# slotESCsmall_S02.net
KiCad netlist of a schematic drawn in Altium Designer
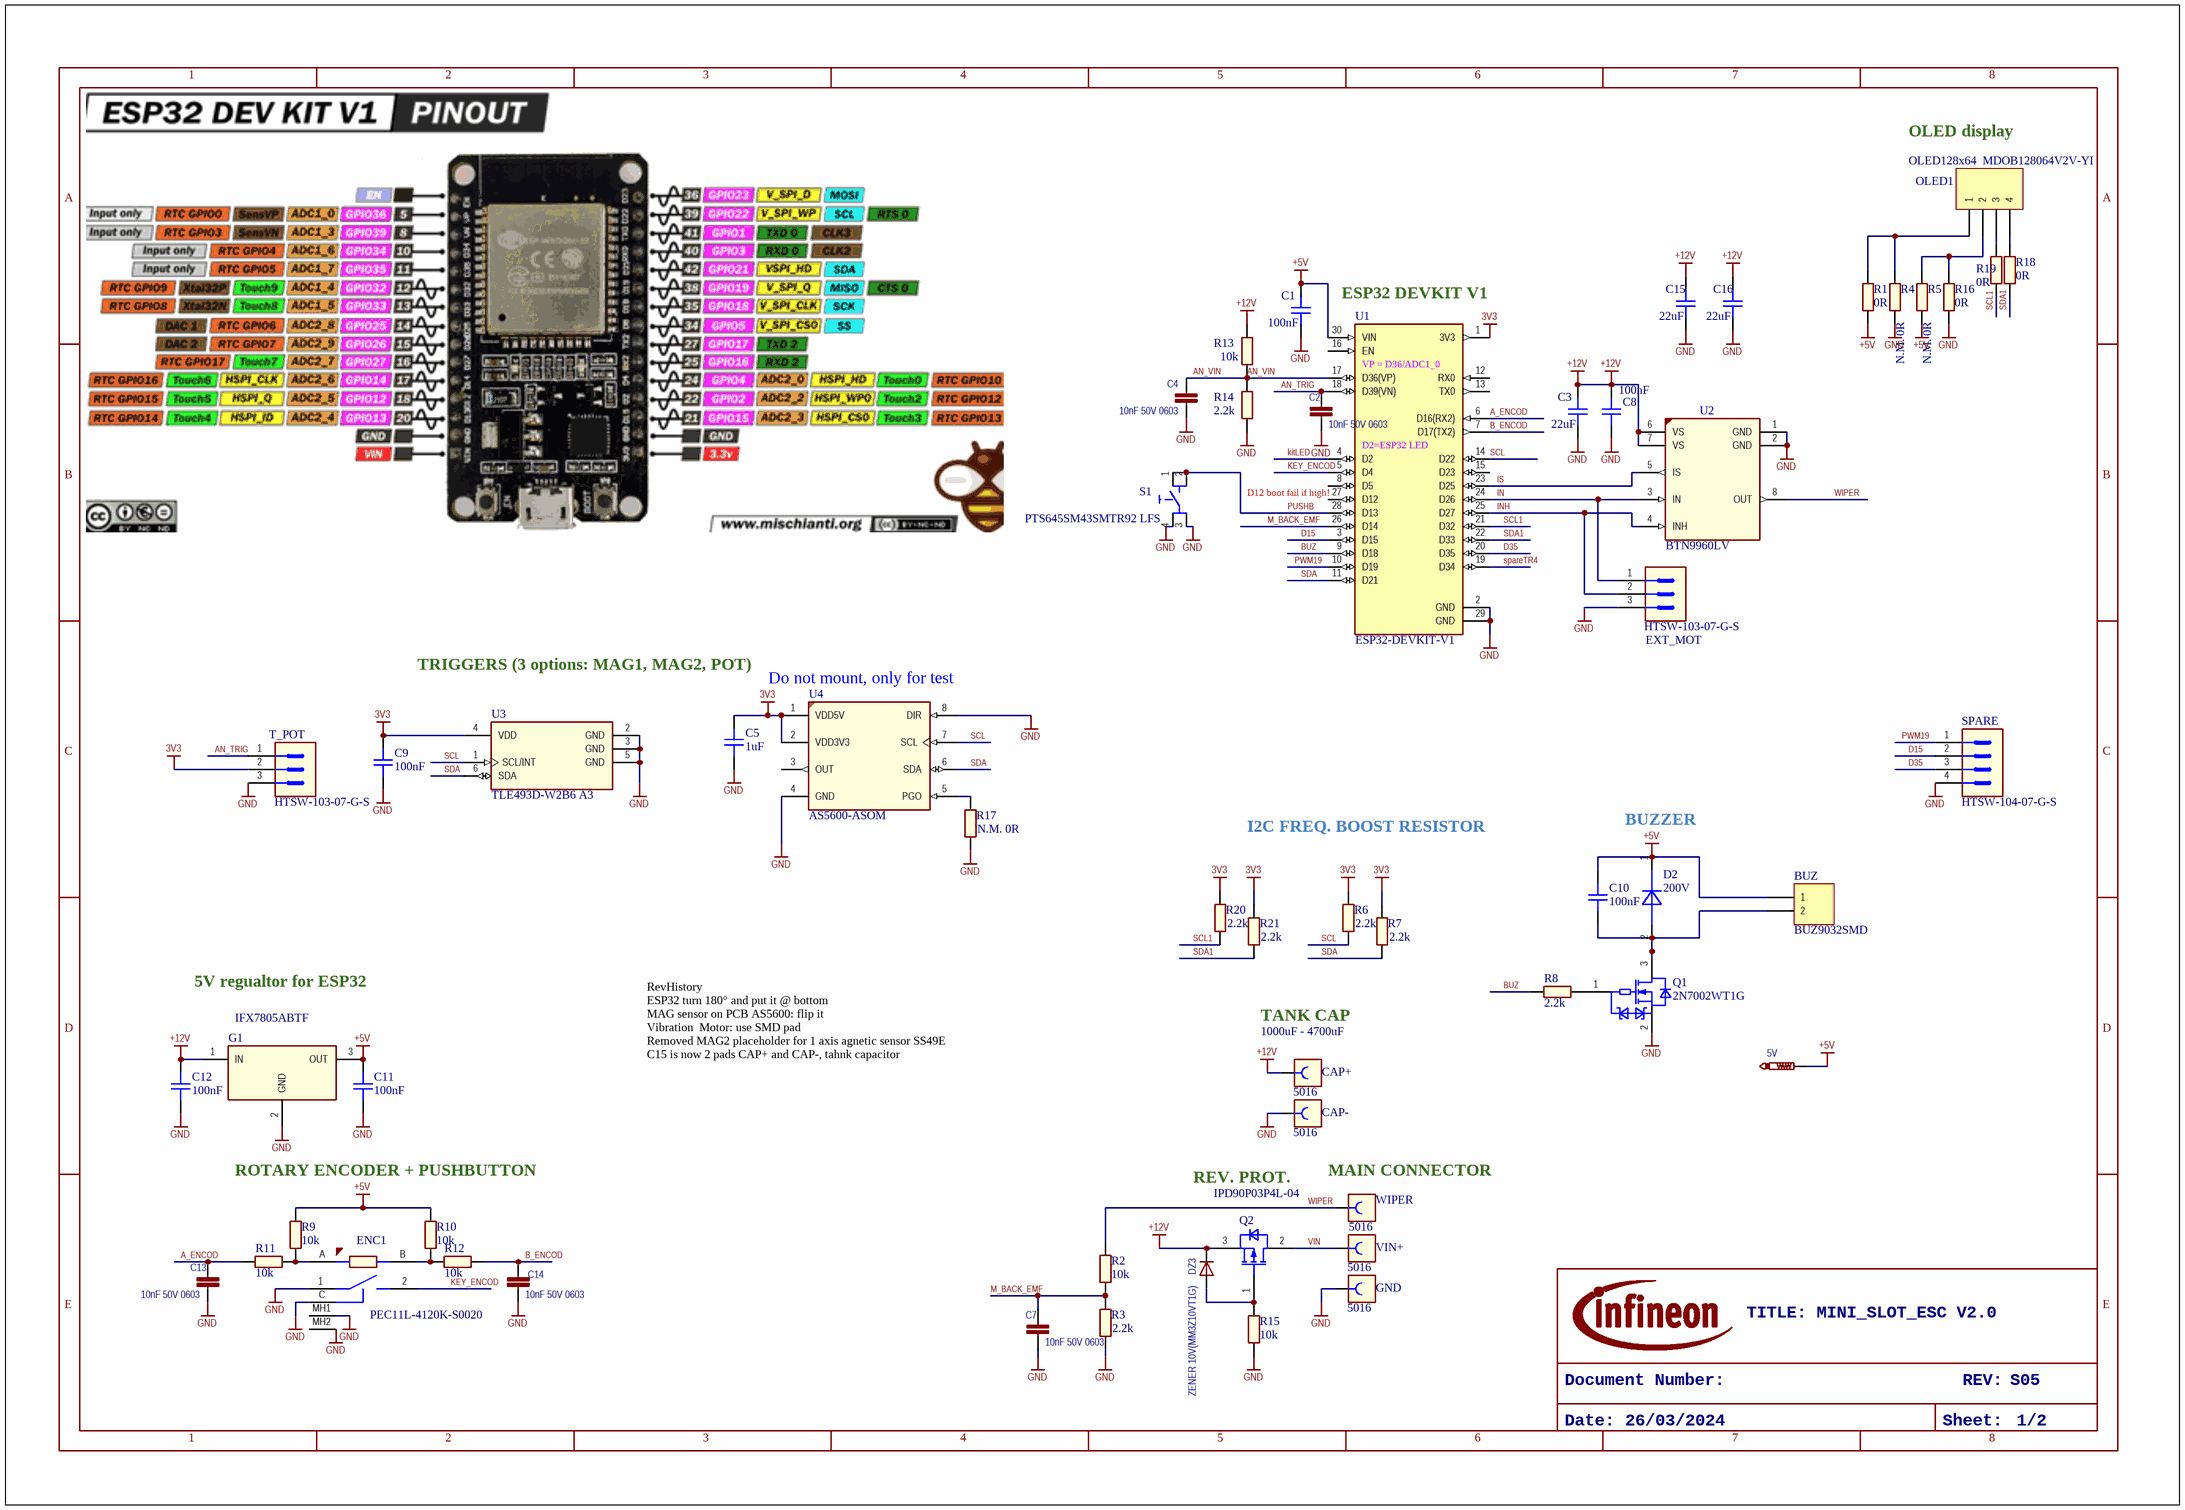
[diagram p0: slotESCsmall_S02.SchDoc]

(export (version "E")
  (design (tool "Eeschema 10.0.6"))
  (components
    (comp (ref "5V")
      (value "NO_POP_Mill-Max 2501-2-00-80-00-00-07-0")
      (footprint "TEST POINT MILL-MAX 2501-2-00-80-00-00-07-0")
      (description "testpad 1mm diameter")
      (libsource (lib "LitixFlexArkasMultiChDemo3") (part "TESTPAD_1MM"))
    )
    (comp (ref "BUZ")
      (value "BUZ9032SMD")
      (footprint "MF_SLOT_ESC_V2.0:BUZ9032_SMD")
      (description "Header, 2-Pin")
      (fields (field (name "PUBLISHER") "Altium Limited"))
      (libsource (lib "Miscellaneous Connectors") (part "Header 2"))
    )
    (comp (ref "C1")
      (value "100nF")
      (footprint "C0603")
      (description "CAP / CERA / 100nF / 25V / 10% / X8R (EIA) / -55°C to 150°C / 0603(1608) / SMD / -")
      (fields (field (name "LEGACY PARTNUMBER") "CAP01008841") (field (name "MANUFACTURER") "MuRata"))
      (libsource (lib "PCBLibraryData") (part "CAP-SGL-STD-02P_00000001"))
    )
    (comp (ref "C2")
      (value "10nF 50V 0603")
      (footprint "C0603")
      (description "CAPACITOR, European symbol")
      (libsource (lib "rcl") (part "C-EUC0402"))
    )
    (comp (ref "C3")
      (value "22uF")
      (footprint "CAPC3225X270N")
      (description "CAP / CERA / 22uF / 25V / 20% / X5R (EIA) / -55°C to 85°C / 1210(3225) / SMD / -")
      (fields (field (name "LEGACY PARTNUMBER") "CAP01005898") (field (name "MANUFACTURER") "MuRata"))
      (libsource (lib "PCBLibraryData") (part "CAP-SGL-STD-02P_00000001"))
    )
    (comp (ref "C4")
      (value "10nF 50V 0603")
      (footprint "C0603")
      (description "CAPACITOR, European symbol")
      (libsource (lib "rcl") (part "C-EUC0402"))
    )
    (comp (ref "C5")
      (value "1uF")
      (footprint "CAPC1608X87N-1")
      (description "CAP / CERA / 1uF / 25V / 20% / X5R (EIA) / -55°C to 85°C / 0603(1608) / SMD / -")
      (fields (field (name "MANUFACTURER") "Wurth Elektronik"))
      (libsource (lib "PCBLibraryData") (part "CAP-SGL-STD-02P_00000001"))
    )
    (comp (ref "C7")
      (value "10nF 50V 0603")
      (footprint "C0603")
      (description "CAPACITOR, European symbol")
      (libsource (lib "rcl") (part "C-EUC0402"))
    )
    (comp (ref "C8")
      (value "100nF")
      (footprint "C0603")
      (description "CAP / CERA / 100nF / 25V / 10% / X8R (EIA) / -55°C to 150°C / 0603(1608) / SMD / -")
      (fields (field (name "LEGACY PARTNUMBER") "CAP01008841") (field (name "MANUFACTURER") "MuRata"))
      (libsource (lib "PCBLibraryData") (part "CAP-SGL-STD-02P_00000001"))
    )
    (comp (ref "C9")
      (value "100nF")
      (footprint "C0603")
      (description "CAP / CERA / 100nF / 25V / 10% / X8R (EIA) / -55°C to 150°C / 0603(1608) / SMD / -")
      (fields (field (name "LEGACY PARTNUMBER") "CAP01008841") (field (name "MANUFACTURER") "MuRata"))
      (libsource (lib "PCBLibraryData") (part "CAP-SGL-STD-02P_00000001"))
    )
    (comp (ref "C10")
      (value "100nF")
      (footprint "C0603")
      (description "CAP / CERA / 100nF / 25V / 10% / X8R (EIA) / -55°C to 150°C / 0603(1608) / SMD / -")
      (fields (field (name "LEGACY PARTNUMBER") "CAP01008841") (field (name "MANUFACTURER") "MuRata"))
      (libsource (lib "PCBLibraryData") (part "CAP-SGL-STD-02P_00000001"))
    )
    (comp (ref "C11")
      (value "100nF")
      (footprint "C0603")
      (description "CAP / CERA / 100nF / 25V / 10% / X8R (EIA) / -55°C to 150°C / 0603(1608) / SMD / -")
      (fields (field (name "LEGACY PARTNUMBER") "CAP01008841") (field (name "MANUFACTURER") "MuRata"))
      (libsource (lib "PCBLibraryData") (part "CAP-SGL-STD-02P_00000001"))
    )
    (comp (ref "C12")
      (value "100nF")
      (footprint "C0603")
      (description "CAP / CERA / 100nF / 25V / 10% / X8R (EIA) / -55°C to 150°C / 0603(1608) / SMD / -")
      (fields (field (name "LEGACY PARTNUMBER") "CAP01008841") (field (name "MANUFACTURER") "MuRata"))
      (libsource (lib "PCBLibraryData") (part "CAP-SGL-STD-02P_00000001"))
    )
    (comp (ref "C13")
      (value "10nF 50V 0603")
      (footprint "C0603")
      (description "CAPACITOR, European symbol")
      (libsource (lib "rcl") (part "C-EUC0402"))
    )
    (comp (ref "C14")
      (value "10nF 50V 0603")
      (footprint "C0603")
      (description "CAPACITOR, European symbol")
      (libsource (lib "rcl") (part "C-EUC0402"))
    )
    (comp (ref "C15")
      (value "22uF")
      (footprint "CAPC3225X270N")
      (description "CAP / CERA / 22uF / 25V / 20% / X5R (EIA) / -55°C to 85°C / 1210(3225) / SMD / -")
      (fields (field (name "LEGACY PARTNUMBER") "CAP01005898") (field (name "MANUFACTURER") "MuRata"))
      (libsource (lib "PCBLibraryData") (part "CAP-SGL-STD-02P_00000001"))
    )
    (comp (ref "C16")
      (value "22uF")
      (footprint "CAPC3225X270N")
      (description "CAP / CERA / 22uF / 25V / 20% / X5R (EIA) / -55°C to 85°C / 1210(3225) / SMD / -")
      (fields (field (name "LEGACY PARTNUMBER") "CAP01005898") (field (name "MANUFACTURER") "MuRata"))
      (libsource (lib "PCBLibraryData") (part "CAP-SGL-STD-02P_00000001"))
    )
    (comp (ref "CAP+")
      (value "5016")
      (footprint "CON-SMD-TP-5016")
      (description "Test Point, Compact, Surface Mount, Finish- Silver Plate")
      (fields
        (field (name "LEGACY PARTNUMBER") "CON01501019")
        (field (name "MANUFACTURER") "Keystone Electronics Corp.")
      )
      (libsource (lib "PCBLibraryData") (part "connector_1_f"))
    )
    (comp (ref "CAP-")
      (value "5016")
      (footprint "CON-SMD-TP-5016")
      (description "Test Point, Compact, Surface Mount, Finish- Silver Plate")
      (fields
        (field (name "LEGACY PARTNUMBER") "CON01501019")
        (field (name "MANUFACTURER") "Keystone Electronics Corp.")
      )
      (libsource (lib "PCBLibraryData") (part "connector_1_f"))
    )
    (comp (ref "D2")
      (value "200V")
      (footprint "DIO-SMD-RF05VYM2SFH")
      (description "Super Fast Recovery Diode")
      (fields (field (name "MANUFACTURER") "ROHM Semiconductors"))
      (libsource (lib "PCBLibraryData") (part "d_std_a"))
    )
    (comp (ref "DZ3")
      (value "ZENER 10V(MM3Z10VT1G)")
      (footprint "SOD323")
      (description "Zener 10V MM3Z10VST1G")
      (libsource (lib "000_Self_made_Gernot") (part "NXP_BAT46WJ"))
    )
    (comp (ref "ENC1")
      (value "PEC11L-4120K-S0020")
      (footprint "SW-THT-PEC11L-4XXXK-SXXXX")
      (description "11 mm Low Profile Encoder")
      (fields (field (name "MANUFACTURER") "Bourns"))
      (libsource (lib "PCBLibraryData") (part "PEC11L-4XXXK-SXXXX"))
    )
    (comp (ref "EXT_MOT")
      (value "HTSW-103-07-G-S")
      (footprint "CON-THT-2.54-3-1-8.38")
      (description "Through hole .025 SQ Post Header, 2.54mm pitch, 3 pin, vertical, single row")
      (fields (field (name "LEGACY PARTNUMBER") "CON00000054") (field (name "MANUFACTURER") "Samtec"))
      (libsource (lib "PCBLibraryData") (part "Header 3"))
    )
    (comp (ref "G1")
      (value "IFX7805ABTF")
      (footprint "TO228P998X235-3N-2-V")
      (description "Three Terminal 1.0A Positive Voltage Regulator")
      (fields
        (field (name "LEGACY PARTNUMBER") "IFX01400731")
        (field (name "MANUFACTURER") "Infineon Technologies")
      )
      (libsource (lib "PCBLibraryData") (part "IFX7805ABTX"))
    )
    (comp (ref "GND")
      (value "5016")
      (footprint "CON-SMD-TP-5016")
      (description "Test Point, Compact, Surface Mount, Finish- Silver Plate")
      (fields
        (field (name "LEGACY PARTNUMBER") "CON01501019")
        (field (name "MANUFACTURER") "Keystone Electronics Corp.")
      )
      (libsource (lib "PCBLibraryData") (part "connector_1_f"))
    )
    (comp (ref "OLED1")
      (value "OLED128x64  MDOB128064V2V-YI")
      (footprint "OLED 128X64 1.3\"")
      (description "Header, 4-Pin")
      (fields (field (name "PUBLISHER") "Altium Limited"))
      (libsource (lib "Miscellaneous Connectors") (part "Header 4"))
    )
    (comp (ref "Q1")
      (value "2N7002WT1G")
      (footprint "SOT65P220X100-3N")
      (fields (field (name "MANUFACTURER") "ON Semiconductor"))
      (libsource (lib "PCBLibraryData") (part "igfet_n_ch_enh_dio_r_g_esd_gs_1g2s3d_3p-2"))
    )
    (comp (ref "Q2")
      (value "IPD90P03P4L-04")
      (footprint "TO228P998X235-3N-2-V")
      (description "OptiMOS - P2 Power-Transistor, P-channel-Enhancement mode, VDS -30V")
      (fields
        (field (name "LEGACY PARTNUMBER") "IFX00200003")
        (field (name "MANUFACTURER") "Infineon Technologies")
      )
      (libsource (lib "PCBLibraryData") (part "igfet_p_ch_enh_dio_1g2d3s_3p"))
    )
    (comp (ref "R1")
      (value "0R")
      (footprint "R0603")
      (description "General Purpose Chip Resistor")
      (fields (field (name "LEGACY PARTNUMBER") "RES00000126") (field (name "MANUFACTURER") "Yageo"))
      (libsource (lib "TLD5542-1MultiCh_V4.3") (part "328011"))
    )
    (comp (ref "R2")
      (value "10k")
      (footprint "R0603")
      (description "RES / STD / 10k / 100mW / 5% / 100ppm/K / -55°C to 155°C / 0603(1608) / SMD / -")
      (fields (field (name "LEGACY PARTNUMBER") "RES01805989") (field (name "MANUFACTURER") "Yageo"))
      (libsource (lib "PCBLibraryData") (part "RES-SGL-STD-02P_00000006"))
    )
    (comp (ref "R3")
      (value "2.2k")
      (footprint "R0603")
      (description "RES / STD / 2.2k / 100mW / 1% / 100ppm/K / -55°C to 155°C / 0603(1608) / SMD / -")
      (fields (field (name "LEGACY PARTNUMBER") "RES00000093") (field (name "MANUFACTURER") "Yageo"))
      (libsource (lib "PCBLibraryData") (part "RES-SGL-STD-02P_00000006"))
    )
    (comp (ref "R4")
      (value "N.M. 0R")
      (footprint "R0603")
      (description "General Purpose Chip Resistor")
      (fields (field (name "LEGACY PARTNUMBER") "RES00000126") (field (name "MANUFACTURER") "Yageo"))
      (libsource (lib "TLD5542-1MultiCh_V4.3") (part "328011"))
    )
    (comp (ref "R5")
      (value "N.M. 0R")
      (footprint "R0603")
      (description "General Purpose Chip Resistor")
      (fields (field (name "LEGACY PARTNUMBER") "RES00000126") (field (name "MANUFACTURER") "Yageo"))
      (libsource (lib "TLD5542-1MultiCh_V4.3") (part "328011"))
    )
    (comp (ref "R6")
      (value "2.2k")
      (footprint "R0603")
      (description "RES / STD / 2.2k / 100mW / 1% / 100ppm/K / -55°C to 155°C / 0603(1608) / SMD / -")
      (fields (field (name "LEGACY PARTNUMBER") "RES00000093") (field (name "MANUFACTURER") "Yageo"))
      (libsource (lib "PCBLibraryData") (part "RES-SGL-STD-02P_00000006"))
    )
    (comp (ref "R7")
      (value "2.2k")
      (footprint "R0603")
      (description "RES / STD / 2.2k / 100mW / 1% / 100ppm/K / -55°C to 155°C / 0603(1608) / SMD / -")
      (fields (field (name "LEGACY PARTNUMBER") "RES00000093") (field (name "MANUFACTURER") "Yageo"))
      (libsource (lib "PCBLibraryData") (part "RES-SGL-STD-02P_00000006"))
    )
    (comp (ref "R8")
      (value "2.2k")
      (footprint "R0603")
      (description "RES / STD / 2.2k / 100mW / 1% / 100ppm/K / -55°C to 155°C / 0603(1608) / SMD / -")
      (fields (field (name "LEGACY PARTNUMBER") "RES00000093") (field (name "MANUFACTURER") "Yageo"))
      (libsource (lib "") (part "RES-SGL-STD-02P_00000006_1"))
    )
    (comp (ref "R9")
      (value "10k")
      (footprint "R0603")
      (description "RES / STD / 10k / 100mW / 5% / 100ppm/K / -55°C to 155°C / 0603(1608) / SMD / -")
      (fields (field (name "LEGACY PARTNUMBER") "RES01805989") (field (name "MANUFACTURER") "Yageo"))
      (libsource (lib "PCBLibraryData") (part "RES-SGL-STD-02P_00000006"))
    )
    (comp (ref "R10")
      (value "10k")
      (footprint "R0603")
      (description "RES / STD / 10k / 100mW / 5% / 100ppm/K / -55°C to 155°C / 0603(1608) / SMD / -")
      (fields (field (name "LEGACY PARTNUMBER") "RES01805989") (field (name "MANUFACTURER") "Yageo"))
      (libsource (lib "PCBLibraryData") (part "RES-SGL-STD-02P_00000006"))
    )
    (comp (ref "R11")
      (value "10k")
      (footprint "R0603")
      (description "RES / STD / 10k / 100mW / 5% / 100ppm/K / -55°C to 155°C / 0603(1608) / SMD / -")
      (fields (field (name "LEGACY PARTNUMBER") "RES01805989") (field (name "MANUFACTURER") "Yageo"))
      (libsource (lib "") (part "RES-SGL-STD-02P_00000006_1"))
    )
    (comp (ref "R12")
      (value "10k")
      (footprint "R0603")
      (description "RES / STD / 10k / 100mW / 5% / 100ppm/K / -55°C to 155°C / 0603(1608) / SMD / -")
      (fields (field (name "LEGACY PARTNUMBER") "RES01805989") (field (name "MANUFACTURER") "Yageo"))
      (libsource (lib "") (part "RES-SGL-STD-02P_00000006_1"))
    )
    (comp (ref "R13")
      (value "10k")
      (footprint "R0603")
      (description "RES / STD / 10k / 100mW / 5% / 100ppm/K / -55°C to 155°C / 0603(1608) / SMD / -")
      (fields (field (name "LEGACY PARTNUMBER") "RES01805989") (field (name "MANUFACTURER") "Yageo"))
      (libsource (lib "PCBLibraryData") (part "RES-SGL-STD-02P_00000006"))
    )
    (comp (ref "R14")
      (value "2.2k")
      (footprint "R0603")
      (description "RES / STD / 2.2k / 100mW / 1% / 100ppm/K / -55°C to 155°C / 0603(1608) / SMD / -")
      (fields (field (name "LEGACY PARTNUMBER") "RES00000093") (field (name "MANUFACTURER") "Yageo"))
      (libsource (lib "PCBLibraryData") (part "RES-SGL-STD-02P_00000006"))
    )
    (comp (ref "R15")
      (value "10k")
      (footprint "R0603")
      (description "RES / STD / 10k / 100mW / 5% / 100ppm/K / -55°C to 155°C / 0603(1608) / SMD / -")
      (fields (field (name "LEGACY PARTNUMBER") "RES01805989") (field (name "MANUFACTURER") "Yageo"))
      (libsource (lib "PCBLibraryData") (part "RES-SGL-STD-02P_00000006"))
    )
    (comp (ref "R16")
      (value "0R")
      (footprint "R0603")
      (description "General Purpose Chip Resistor")
      (fields (field (name "LEGACY PARTNUMBER") "RES00000126") (field (name "MANUFACTURER") "Yageo"))
      (libsource (lib "TLD5542-1MultiCh_V4.3") (part "328011"))
    )
    (comp (ref "R17")
      (value "N.M. 0R")
      (footprint "R0603")
      (description "General Purpose Chip Resistor")
      (fields (field (name "LEGACY PARTNUMBER") "RES00000126") (field (name "MANUFACTURER") "Yageo"))
      (libsource (lib "TLD5542-1MultiCh_V4.3") (part "328011"))
    )
    (comp (ref "R18")
      (value "0R")
      (footprint "R0603")
      (description "General Purpose Chip Resistor")
      (fields (field (name "LEGACY PARTNUMBER") "RES00000126") (field (name "MANUFACTURER") "Yageo"))
      (libsource (lib "TLD5542-1MultiCh_V4.3") (part "328011"))
    )
    (comp (ref "R19")
      (value "0R")
      (footprint "R0603")
      (description "General Purpose Chip Resistor")
      (fields (field (name "LEGACY PARTNUMBER") "RES00000126") (field (name "MANUFACTURER") "Yageo"))
      (libsource (lib "TLD5542-1MultiCh_V4.3") (part "328011"))
    )
    (comp (ref "R20")
      (value "2.2k")
      (footprint "R0603")
      (description "RES / STD / 2.2k / 100mW / 1% / 100ppm/K / -55°C to 155°C / 0603(1608) / SMD / -")
      (fields (field (name "LEGACY PARTNUMBER") "RES00000093") (field (name "MANUFACTURER") "Yageo"))
      (libsource (lib "PCBLibraryData") (part "RES-SGL-STD-02P_00000006"))
    )
    (comp (ref "R21")
      (value "2.2k")
      (footprint "R0603")
      (description "RES / STD / 2.2k / 100mW / 1% / 100ppm/K / -55°C to 155°C / 0603(1608) / SMD / -")
      (fields (field (name "LEGACY PARTNUMBER") "RES00000093") (field (name "MANUFACTURER") "Yageo"))
      (libsource (lib "PCBLibraryData") (part "RES-SGL-STD-02P_00000006"))
    )
    (comp (ref "S1")
      (value "PTS645SM43SMTR92 LFS")
      (footprint "SW-SMD-PTS645SK43SMTR92")
      (description "Tact Switches, Variety of Actuator Lengths")
      (fields (field (name "MANUFACTURER") "C&K"))
      (libsource (lib "PCBLibraryData") (part "sw_c1234_4p"))
    )
    (comp (ref "SPARE")
      (value "HTSW-104-07-G-S")
      (footprint "HDRV4W64P254_1X4_1016X248X838B")
      (description "Through hole .025 SQ Post Header, Hi-Temp Strip, 2.54mm pitch, 4 pin, vertical, single row")
      (fields (field (name "LEGACY PARTNUMBER") "CON01500246") (field (name "MANUFACTURER") "Samtec"))
      (libsource (lib "PCBLibraryData") (part "Header 4"))
    )
    (comp (ref "T_POT")
      (value "HTSW-103-07-G-S")
      (footprint "CON-THT-2.54-3-1-8.38")
      (description "Through hole .025 SQ Post Header, 2.54mm pitch, 3 pin, vertical, single row")
      (fields (field (name "LEGACY PARTNUMBER") "CON00000054") (field (name "MANUFACTURER") "Samtec"))
      (libsource (lib "PCBLibraryData") (part "Header 3"))
    )
    (comp (ref "U1")
      (value "ESP32-DEVKIT-V1")
      (footprint "MODULE_ESP32_DEVKIT_V1")
      (fields (field (name "MF") "Do it"))
      (libsource (lib "ESP32-DEVKIT-V1") (part "ESP32-DEVKIT-V1"))
    )
    (comp (ref "U2")
      (value "BTN9960LV")
      (footprint "IFX-PG-HSOF-7-1-V")
      (description "MOTIX Single Half-Bridge with Integrated Driver IC")
      (fields (field (name "MANUFACTURER") "Infineon Technologies"))
      (libsource (lib "PCBLibraryData") (part "BTN99X0LV"))
    )
    (comp (ref "U3")
      (value "TLE493D-W2B6 A3")
      (footprint "SOP95P280X110-6N-V")
      (description "Low Power 3D Hall Sensor with I2C Interface and Wake Up Function, Temp Range(-40 to 125°C)")
      (fields (field (name "MANUFACTURER") "Infineon Technologies"))
      (libsource (lib "PCBLibraryData") (part "TLE493D-W2B6"))
    )
    (comp (ref "U4")
      (value "AS5600-ASOM")
      (footprint "SOIC127P600X175-8N-9")
      (description "12 Bit Programmable Contactless Potentiometer")
      (fields (field (name "MANUFACTURER") "AMS"))
      (libsource (lib "PCBLibraryData") (part "AS5600"))
    )
    (comp (ref "VIN+")
      (value "5016")
      (footprint "CON-SMD-TP-5016")
      (description "Test Point, Compact, Surface Mount, Finish- Silver Plate")
      (fields
        (field (name "LEGACY PARTNUMBER") "CON01501019")
        (field (name "MANUFACTURER") "Keystone Electronics Corp.")
      )
      (libsource (lib "PCBLibraryData") (part "connector_1_f"))
    )
    (comp (ref "WIPER")
      (value "5016")
      (footprint "CON-SMD-TP-5016")
      (description "Test Point, Compact, Surface Mount, Finish- Silver Plate")
      (fields
        (field (name "LEGACY PARTNUMBER") "CON01501019")
        (field (name "MANUFACTURER") "Keystone Electronics Corp.")
      )
      (libsource (lib "PCBLibraryData") (part "connector_1_f"))
    )
  )
  (nets
    (net (code "1") (name "+5V") (class "Default")
      (node (ref "5V") (pin "1") (pinfunction "TP_1") (pintype "passive"))
      (node (ref "BUZ") (pin "1") (pinfunction "1_1") (pintype "passive"))
      (node (ref "C1") (pin "2") (pinfunction "2_2") (pintype "passive"))
      (node (ref "C10") (pin "2") (pinfunction "2_2") (pintype "passive"))
      (node (ref "C11") (pin "2") (pinfunction "2_2") (pintype "passive"))
      (node (ref "D2") (pin "1") (pinfunction "Cathode_1") (pintype "passive"))
      (node (ref "G1") (pin "3") (pinfunction "OUT_3") (pintype "power_in"))
      (node (ref "R1") (pin "1") (pinfunction "1_1") (pintype "passive"))
      (node (ref "R10") (pin "2") (pinfunction "2_2") (pintype "passive"))
      (node (ref "R5") (pin "1") (pinfunction "1_1") (pintype "passive"))
      (node (ref "R9") (pin "2") (pinfunction "2_2") (pintype "passive"))
      (node (ref "U1") (pin "30") (pinfunction "VIN_30") (pintype "input"))
    )
    (net (code "2") (name "+12V") (class "Default")
      (node (ref "C12") (pin "2") (pinfunction "2_2") (pintype "passive"))
      (node (ref "C15") (pin "2") (pinfunction "2_2") (pintype "passive"))
      (node (ref "C16") (pin "2") (pinfunction "2_2") (pintype "passive"))
      (node (ref "C3") (pin "2") (pinfunction "2_2") (pintype "passive"))
      (node (ref "C8") (pin "2") (pinfunction "2_2") (pintype "passive"))
      (node (ref "CAP+") (pin "1") (pinfunction "1_1") (pintype "passive"))
      (node (ref "DZ3") (pin "K") (pinfunction "K_K") (pintype "passive"))
      (node (ref "G1") (pin "1") (pinfunction "IN_1") (pintype "power_in"))
      (node (ref "Q2") (pin "3") (pinfunction "SOURCE_3") (pintype "passive"))
      (node (ref "R13") (pin "2") (pinfunction "2_2") (pintype "passive"))
      (node (ref "U2") (pin "6") (pinfunction "VS_6") (pintype "power_in"))
      (node (ref "U2") (pin "7") (pinfunction "VS_7") (pintype "power_in"))
    )
    (net (code "3") (name "/AN_TRIG") (class "Default")
      (node (ref "C2") (pin "2") (pinfunction "2_2") (pintype "passive"))
      (node (ref "T_POT") (pin "1") (pinfunction "1_1") (pintype "passive"))
      (node (ref "U1") (pin "18") (pinfunction "D39(VN)_18") (pintype "bidirectional"))
    )
    (net (code "4") (name "/AN_VIN") (class "Default")
      (node (ref "C4") (pin "2") (pinfunction "2_2") (pintype "passive"))
      (node (ref "R13") (pin "1") (pinfunction "1_1") (pintype "passive"))
      (node (ref "R14") (pin "2") (pinfunction "2_2") (pintype "passive"))
      (node (ref "U1") (pin "17") (pinfunction "D36(VP)_17") (pintype "bidirectional"))
    )
    (net (code "5") (name "/A_ENCOD") (class "Default")
      (node (ref "C13") (pin "2") (pinfunction "2_2") (pintype "passive"))
      (node (ref "R11") (pin "2") (pinfunction "2_2") (pintype "passive"))
      (node (ref "U1") (pin "6") (pinfunction "D16(RX2)_6") (pintype "input"))
    )
    (net (code "6") (name "/BUZ") (class "Default")
      (node (ref "R8") (pin "2") (pinfunction "2_2") (pintype "passive"))
      (node (ref "U1") (pin "9") (pinfunction "D18_9") (pintype "bidirectional"))
    )
    (net (code "7") (name "/B_ENCOD") (class "Default")
      (node (ref "C14") (pin "2") (pinfunction "2_2") (pintype "passive"))
      (node (ref "R12") (pin "1") (pinfunction "1_1") (pintype "passive"))
      (node (ref "U1") (pin "7") (pinfunction "D17(TX2)_7") (pintype "output"))
    )
    (net (code "8") (name "/D15") (class "Default")
      (node (ref "SPARE") (pin "2") (pinfunction "2_2") (pintype "passive"))
      (node (ref "U1") (pin "3") (pinfunction "D15_3") (pintype "bidirectional"))
    )
    (net (code "9") (name "/D35") (class "Default")
      (node (ref "SPARE") (pin "3") (pinfunction "3_3") (pintype "passive"))
      (node (ref "U1") (pin "20") (pinfunction "D35_20") (pintype "bidirectional"))
    )
    (net (code "10") (name "/IN") (class "Default")
      (node (ref "EXT_MOT") (pin "1") (pinfunction "1_1") (pintype "passive"))
      (node (ref "U1") (pin "24") (pinfunction "D26_24") (pintype "bidirectional"))
      (node (ref "U2") (pin "3") (pinfunction "IN_3") (pintype "input"))
    )
    (net (code "11") (name "/INH") (class "Default")
      (node (ref "EXT_MOT") (pin "2") (pinfunction "2_2") (pintype "passive"))
      (node (ref "U1") (pin "25") (pinfunction "D27_25") (pintype "bidirectional"))
      (node (ref "U2") (pin "4") (pinfunction "INH_4") (pintype "input"))
    )
    (net (code "12") (name "/IS") (class "Default")
      (node (ref "U1") (pin "23") (pinfunction "D25_23") (pintype "bidirectional"))
      (node (ref "U2") (pin "5") (pinfunction "IS_5") (pintype "output"))
    )
    (net (code "13") (name "/KEY_ENCOD") (class "Default")
      (node (ref "ENC1") (pin "2") (pinfunction "2_2") (pintype "passive"))
      (node (ref "U1") (pin "5") (pinfunction "D4_5") (pintype "bidirectional"))
    )
    (net (code "14") (name "/M_BACK_EMF") (class "Default")
      (node (ref "C7") (pin "2") (pinfunction "2_2") (pintype "passive"))
      (node (ref "R2") (pin "1") (pinfunction "1_1") (pintype "passive"))
      (node (ref "R3") (pin "2") (pinfunction "2_2") (pintype "passive"))
      (node (ref "U1") (pin "26") (pinfunction "D14_26") (pintype "bidirectional"))
    )
    (net (code "15") (name "/PUSHB") (class "Default")
      (node (ref "S1") (pin "1") (pintype "passive"))
      (node (ref "S1") (pin "2") (pintype "passive"))
      (node (ref "U1") (pin "28") (pinfunction "D13_28") (pintype "bidirectional"))
    )
    (net (code "16") (name "/PWM19") (class "Default")
      (node (ref "SPARE") (pin "1") (pinfunction "1_1") (pintype "passive"))
      (node (ref "U1") (pin "10") (pinfunction "D19_10") (pintype "bidirectional"))
    )
    (net (code "17") (name "/SCL") (class "Default")
      (node (ref "R6") (pin "1") (pinfunction "1_1") (pintype "passive"))
      (node (ref "U1") (pin "14") (pinfunction "D22_14") (pintype "bidirectional"))
      (node (ref "U3") (pin "1") (pinfunction "SCL/INT_1") (pintype "input"))
      (node (ref "U4") (pin "7") (pinfunction "SCL_7") (pintype "input"))
    )
    (net (code "18") (name "/SCL1") (class "Default")
      (node (ref "R19") (pin "1") (pinfunction "1_1") (pintype "passive"))
      (node (ref "R20") (pin "1") (pinfunction "1_1") (pintype "passive"))
      (node (ref "U1") (pin "21") (pinfunction "D32_21") (pintype "bidirectional"))
    )
    (net (code "19") (name "/SDA") (class "Default")
      (node (ref "R7") (pin "1") (pinfunction "1_1") (pintype "passive"))
      (node (ref "U1") (pin "11") (pinfunction "D21_11") (pintype "bidirectional"))
      (node (ref "U3") (pin "6") (pinfunction "SDA_6") (pintype "bidirectional"))
      (node (ref "U4") (pin "6") (pinfunction "SDA_6") (pintype "bidirectional"))
    )
    (net (code "20") (name "/SDA1") (class "Default")
      (node (ref "R18") (pin "1") (pinfunction "1_1") (pintype "passive"))
      (node (ref "R21") (pin "1") (pinfunction "1_1") (pintype "passive"))
      (node (ref "U1") (pin "22") (pinfunction "D33_22") (pintype "bidirectional"))
    )
    (net (code "21") (name "/VIN") (class "Default")
      (node (ref "Q2") (pin "2") (pinfunction "DRAIN_2") (pintype "passive"))
      (node (ref "VIN+") (pin "1") (pinfunction "1_1") (pintype "passive"))
    )
    (net (code "22") (name "/WIPER") (class "Default")
      (node (ref "R2") (pin "2") (pinfunction "2_2") (pintype "passive"))
      (node (ref "U2") (pin "8") (pinfunction "OUT_8") (pintype "output"))
      (node (ref "WIPER") (pin "1") (pinfunction "1_1") (pintype "passive"))
    )
    (net (code "23") (name "/kitLED") (class "Default")
      (node (ref "U1") (pin "4") (pinfunction "D2_4") (pintype "bidirectional"))
    )
    (net (code "24") (name "/spareTR4") (class "Default")
      (node (ref "U1") (pin "19") (pinfunction "D34_19") (pintype "bidirectional"))
    )
    (net (code "25") (name "3V3") (class "Default")
      (node (ref "C5") (pin "2") (pinfunction "2_2") (pintype "passive"))
      (node (ref "C9") (pin "2") (pinfunction "2_2") (pintype "passive"))
      (node (ref "R20") (pin "2") (pinfunction "2_2") (pintype "passive"))
      (node (ref "R21") (pin "2") (pinfunction "2_2") (pintype "passive"))
      (node (ref "R6") (pin "2") (pinfunction "2_2") (pintype "passive"))
      (node (ref "R7") (pin "2") (pinfunction "2_2") (pintype "passive"))
      (node (ref "T_POT") (pin "2") (pinfunction "2_2") (pintype "passive"))
      (node (ref "U1") (pin "1") (pinfunction "3V3_1") (pintype "output"))
      (node (ref "U3") (pin "4") (pinfunction "VDD_4") (pintype "power_in"))
      (node (ref "U4") (pin "1") (pinfunction "VDD5V_1") (pintype "power_in"))
      (node (ref "U4") (pin "2") (pinfunction "VDD3V3_2") (pintype "power_in"))
    )
    (net (code "26") (name "GND") (class "Default")
      (node (ref "C1") (pin "1") (pinfunction "1_1") (pintype "passive"))
      (node (ref "C11") (pin "1") (pinfunction "1_1") (pintype "passive"))
      (node (ref "C12") (pin "1") (pinfunction "1_1") (pintype "passive"))
      (node (ref "C13") (pin "1") (pinfunction "1_1") (pintype "passive"))
      (node (ref "C14") (pin "1") (pinfunction "1_1") (pintype "passive"))
      (node (ref "C15") (pin "1") (pinfunction "1_1") (pintype "passive"))
      (node (ref "C16") (pin "1") (pinfunction "1_1") (pintype "passive"))
      (node (ref "C2") (pin "1") (pinfunction "1_1") (pintype "passive"))
      (node (ref "C3") (pin "1") (pinfunction "1_1") (pintype "passive"))
      (node (ref "C4") (pin "1") (pinfunction "1_1") (pintype "passive"))
      (node (ref "C5") (pin "1") (pinfunction "1_1") (pintype "passive"))
      (node (ref "C7") (pin "1") (pinfunction "1_1") (pintype "passive"))
      (node (ref "C8") (pin "1") (pinfunction "1_1") (pintype "passive"))
      (node (ref "C9") (pin "1") (pinfunction "1_1") (pintype "passive"))
      (node (ref "CAP-") (pin "1") (pinfunction "1_1") (pintype "passive"))
      (node (ref "ENC1") (pin "1") (pinfunction "1_1") (pintype "passive"))
      (node (ref "ENC1") (pin "C") (pinfunction "C_C") (pintype "passive"))
      (node (ref "EXT_MOT") (pin "3") (pinfunction "3_3") (pintype "passive"))
      (node (ref "G1") (pin "2") (pinfunction "GND_2") (pintype "power_in"))
      (node (ref "GND") (pin "1") (pinfunction "1_1") (pintype "passive"))
      (node (ref "Q1") (pin "2") (pinfunction "S_2") (pintype "passive"))
      (node (ref "R14") (pin "1") (pinfunction "1_1") (pintype "passive"))
      (node (ref "R15") (pin "1") (pinfunction "1_1") (pintype "passive"))
      (node (ref "R16") (pin "1") (pinfunction "1_1") (pintype "passive"))
      (node (ref "R17") (pin "1") (pinfunction "1_1") (pintype "passive"))
      (node (ref "R3") (pin "1") (pinfunction "1_1") (pintype "passive"))
      (node (ref "R4") (pin "1") (pinfunction "1_1") (pintype "passive"))
      (node (ref "S1") (pin "3") (pintype "passive"))
      (node (ref "S1") (pin "4") (pintype "passive"))
      (node (ref "SPARE") (pin "4") (pinfunction "4_4") (pintype "passive"))
      (node (ref "T_POT") (pin "3") (pinfunction "3_3") (pintype "passive"))
      (node (ref "U1") (pin "2") (pinfunction "GND_2") (pintype "power_in"))
      (node (ref "U1") (pin "29") (pinfunction "GND_29") (pintype "power_in"))
      (node (ref "U2") (pin "1") (pinfunction "GND_1") (pintype "power_in"))
      (node (ref "U2") (pin "2") (pinfunction "GND_2") (pintype "power_in"))
      (node (ref "U3") (pin "2") (pinfunction "GND_2") (pintype "power_in"))
      (node (ref "U3") (pin "3") (pinfunction "GND_3") (pintype "power_in"))
      (node (ref "U3") (pin "5") (pinfunction "GND_5") (pintype "power_in"))
      (node (ref "U4") (pin "4") (pinfunction "GND_4") (pintype "power_in"))
      (node (ref "U4") (pin "8") (pinfunction "DIR_8") (pintype "input"))
    )
    (net (code "27") (name "Net-(D2-Anode)") (class "Default")
      (node (ref "BUZ") (pin "2") (pinfunction "2_2") (pintype "passive"))
      (node (ref "C10") (pin "1") (pinfunction "1_1") (pintype "passive"))
      (node (ref "D2") (pin "2") (pinfunction "Anode_2") (pintype "passive"))
      (node (ref "Q1") (pin "3") (pinfunction "D_3") (pintype "passive"))
    )
    (net (code "28") (name "Net-(ENC1-PadA)") (class "Default")
      (node (ref "ENC1") (pin "A") (pinfunction "A_A") (pintype "passive"))
      (node (ref "R11") (pin "1") (pinfunction "1_1") (pintype "passive"))
      (node (ref "R9") (pin "1") (pinfunction "1_1") (pintype "passive"))
    )
    (net (code "29") (name "Net-(ENC1-PadB)") (class "Default")
      (node (ref "ENC1") (pin "B") (pinfunction "B_B") (pintype "passive"))
      (node (ref "R10") (pin "1") (pinfunction "1_1") (pintype "passive"))
      (node (ref "R12") (pin "2") (pinfunction "2_2") (pintype "passive"))
    )
    (net (code "30") (name "Net-(OLED1-Pad1)") (class "Default")
      (node (ref "OLED1") (pin "1") (pinfunction "1_1") (pintype "passive"))
      (node (ref "R1") (pin "2") (pinfunction "2_2") (pintype "passive"))
      (node (ref "R4") (pin "2") (pinfunction "2_2") (pintype "passive"))
    )
    (net (code "31") (name "Net-(OLED1-Pad2)") (class "Default")
      (node (ref "OLED1") (pin "2") (pinfunction "2_2") (pintype "passive"))
      (node (ref "R16") (pin "2") (pinfunction "2_2") (pintype "passive"))
      (node (ref "R5") (pin "2") (pinfunction "2_2") (pintype "passive"))
    )
    (net (code "32") (name "Net-(OLED1-Pad3)") (class "Default")
      (node (ref "OLED1") (pin "3") (pinfunction "3_3") (pintype "passive"))
      (node (ref "R19") (pin "2") (pinfunction "2_2") (pintype "passive"))
    )
    (net (code "33") (name "Net-(OLED1-Pad4)") (class "Default")
      (node (ref "OLED1") (pin "4") (pinfunction "4_4") (pintype "passive"))
      (node (ref "R18") (pin "2") (pinfunction "2_2") (pintype "passive"))
    )
    (net (code "34") (name "Net-(Q1-G)") (class "Default")
      (node (ref "Q1") (pin "1") (pinfunction "G_1") (pintype "passive"))
      (node (ref "R8") (pin "1") (pinfunction "1_1") (pintype "passive"))
    )
    (net (code "35") (name "Net-(Q2-GATE)") (class "Default")
      (node (ref "DZ3") (pin "A") (pinfunction "A_A") (pintype "passive"))
      (node (ref "Q2") (pin "1") (pinfunction "GATE_1") (pintype "passive"))
      (node (ref "R15") (pin "2") (pinfunction "2_2") (pintype "passive"))
    )
    (net (code "36") (name "Net-(U4-PGO)") (class "Default")
      (node (ref "R17") (pin "2") (pinfunction "2_2") (pintype "passive"))
      (node (ref "U4") (pin "5") (pinfunction "PGO_5") (pintype "input"))
    )
    (net (code "37") (name "unconnected-(ENC1-PadMH1)") (class "Default")
      (node (ref "ENC1") (pin "MH1") (pinfunction "MH1_MH1") (pintype "passive"))
    )
    (net (code "38") (name "unconnected-(ENC1-PadMH2)") (class "Default")
      (node (ref "ENC1") (pin "MH2") (pinfunction "MH2_MH2") (pintype "passive"))
    )
    (net (code "39") (name "unconnected-(U1-D5-Pad8)") (class "Default")
      (node (ref "U1") (pin "8") (pinfunction "D5_8") (pintype "bidirectional"))
    )
    (net (code "40") (name "unconnected-(U1-D12-Pad27)") (class "Default")
      (node (ref "U1") (pin "27") (pinfunction "D12_27") (pintype "bidirectional"))
    )
    (net (code "41") (name "unconnected-(U1-D23-Pad15)") (class "Default")
      (node (ref "U1") (pin "15") (pinfunction "D23_15") (pintype "bidirectional"))
    )
    (net (code "42") (name "unconnected-(U1-EN-Pad16)") (class "Default")
      (node (ref "U1") (pin "16") (pinfunction "EN_16") (pintype "input"))
    )
    (net (code "43") (name "unconnected-(U1-RX0-Pad12)") (class "Default")
      (node (ref "U1") (pin "12") (pinfunction "RX0_12") (pintype "input"))
    )
    (net (code "44") (name "unconnected-(U1-TX0-Pad13)") (class "Default")
      (node (ref "U1") (pin "13") (pinfunction "TX0_13") (pintype "output"))
    )
    (net (code "45") (name "unconnected-(U4-OUT-Pad3)") (class "Default")
      (node (ref "U4") (pin "3") (pinfunction "OUT_3") (pintype "output"))
    )
  )
)
